# 60_WIFI_RTL8723DS.net
KiCad netlist of a schematic drawn in Altium Designer
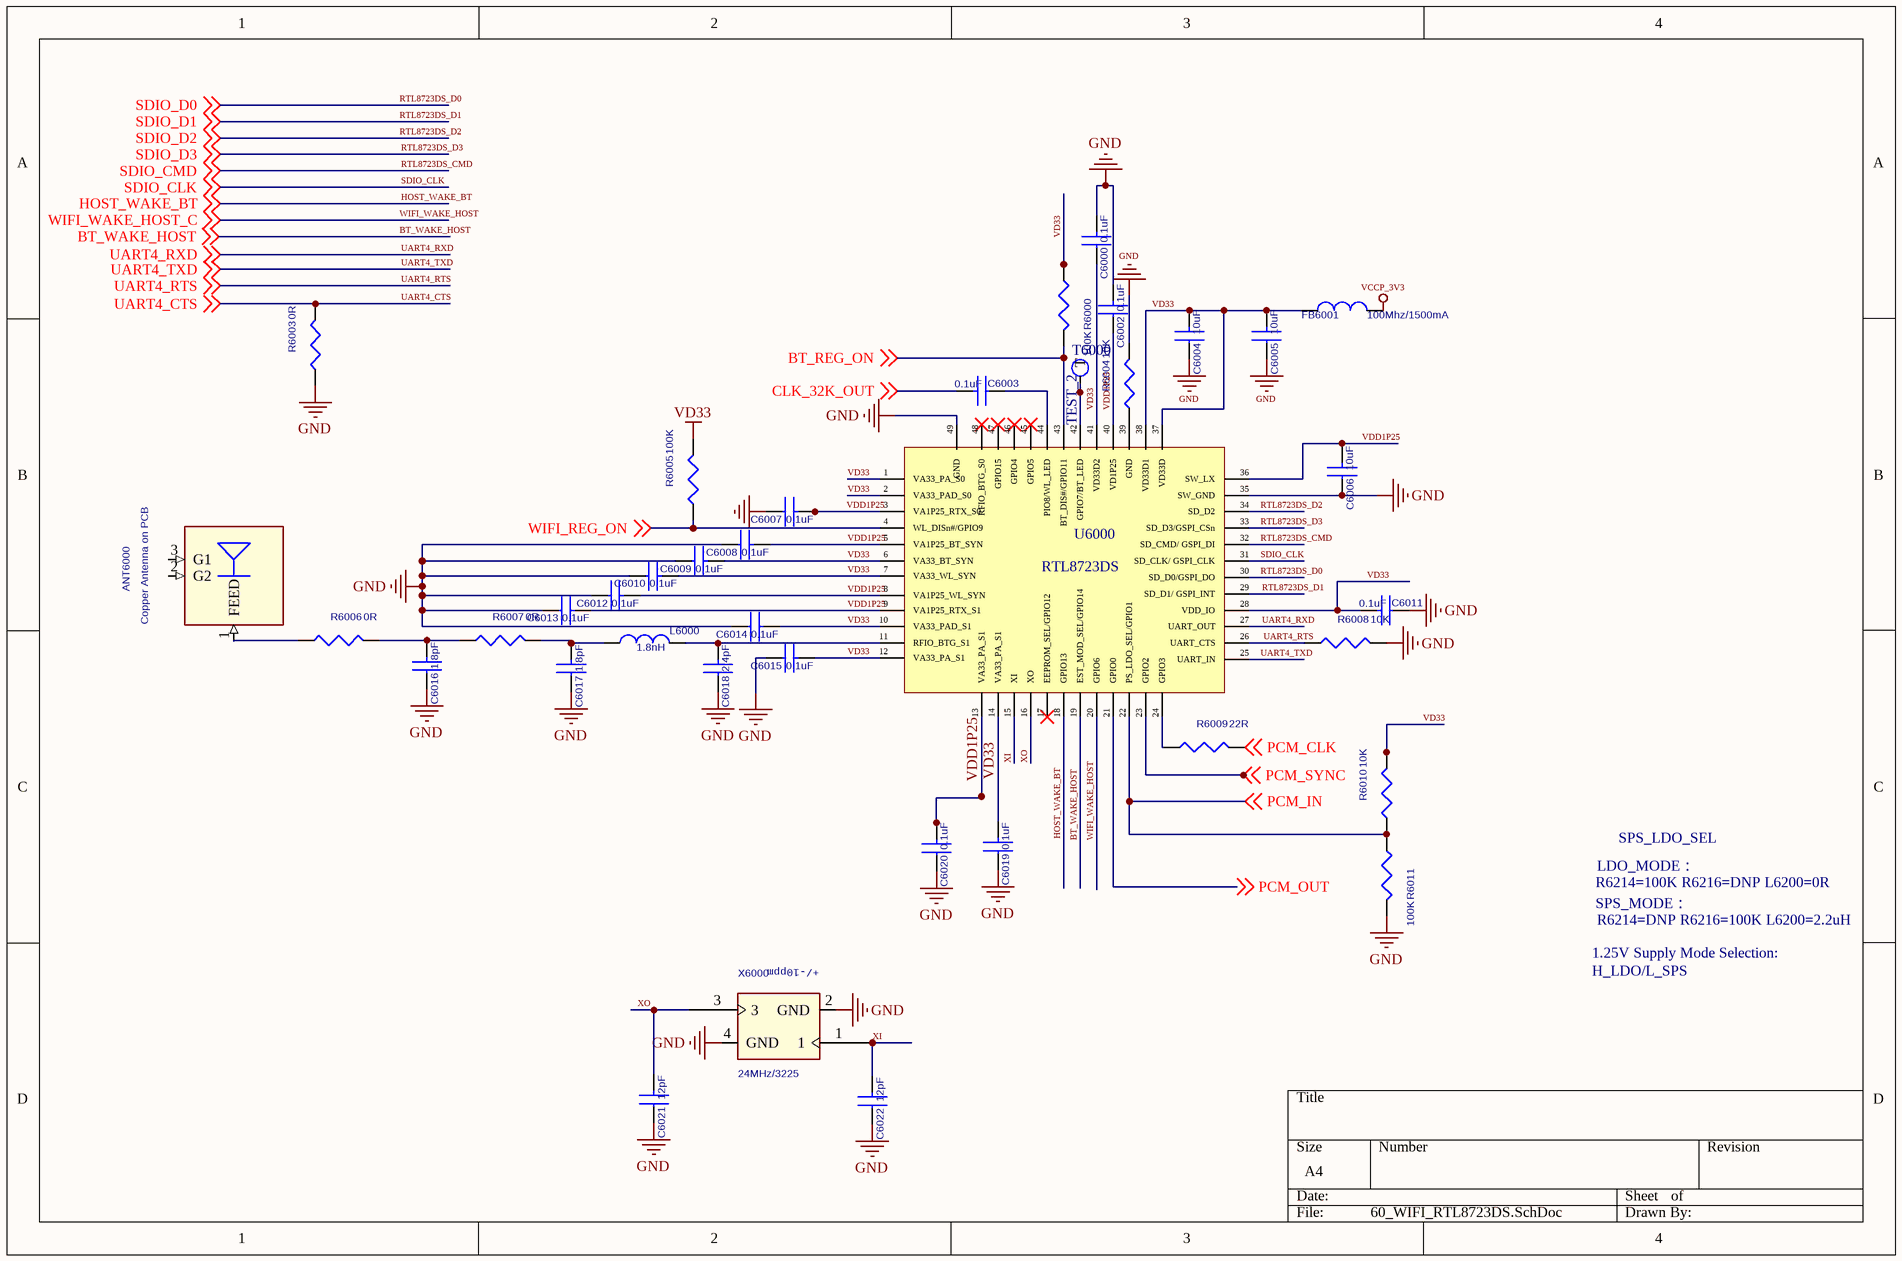
[diagram p0: 60_WIFI_RTL8723DS.SchDoc]

(export (version "E")
  (design (tool "Eeschema 10.0.6"))
  (components
    (comp (ref "ANT6000")
      (value "N/A")
      (footprint "ANT")
      (fields
        (field (name "MANUFACTURER PART NUMBER") "IIFA_CC2420")
        (field (name "NOTE") "Copper Antenna on PCB")
      )
      (libsource (lib "RK3128(Y2)_2X16BIT_V0_1_20201001") (part "ANT_IIFA_CC2420_32mil_MIR"))
    )
    (comp (ref "C6000") (value "0.1uF") (footprint "C0402") (libsource (lib "*") (part "C/0603")))
    (comp (ref "C6002") (value "0.1uF") (footprint "C0402") (libsource (lib "*") (part "C/0603")))
    (comp (ref "C6003") (value "0.1uF") (footprint "C0402") (libsource (lib "*") (part "C/0603")))
    (comp (ref "C6004") (value "10uF") (footprint "C0603") (libsource (lib "*") (part "C/0603")))
    (comp (ref "C6005") (value "10uF") (footprint "C0603") (libsource (lib "*") (part "C/0603")))
    (comp (ref "C6006") (value "10uF") (footprint "C0603") (libsource (lib "*") (part "C/0603")))
    (comp (ref "C6007") (value "0.1uF") (footprint "C0402") (libsource (lib "*") (part "C/0603")))
    (comp (ref "C6008") (value "0.1uF") (footprint "C0402") (libsource (lib "*") (part "C/0603")))
    (comp (ref "C6009") (value "0.1uF") (footprint "C0402") (libsource (lib "*") (part "C/0603")))
    (comp (ref "C6010") (value "0.1uF") (footprint "C0402") (libsource (lib "*") (part "C/0603")))
    (comp (ref "C6011") (value "0.1uF") (footprint "C0402") (libsource (lib "*") (part "C/0603")))
    (comp (ref "C6012") (value "0.1uF") (footprint "C0402") (libsource (lib "*") (part "C/0603")))
    (comp (ref "C6013") (value "0.1uF") (footprint "C0402") (libsource (lib "*") (part "C/0603")))
    (comp (ref "C6014") (value "0.1uF") (footprint "C0402") (libsource (lib "*") (part "C/0603")))
    (comp (ref "C6015") (value "0.1uF") (footprint "C0402") (libsource (lib "*") (part "C/0603")))
    (comp (ref "C6016") (value "1.8pF") (footprint "C0402") (libsource (lib "*") (part "C/0603")))
    (comp (ref "C6017") (value "1.8pF") (footprint "C0402") (libsource (lib "*") (part "C/0603")))
    (comp (ref "C6018") (value "2.4pF") (footprint "C0402") (libsource (lib "*") (part "C/0603")))
    (comp (ref "C6019") (value "0.1uF") (footprint "C0402") (libsource (lib "*") (part "C/0603")))
    (comp (ref "C6020") (value "0.1uF") (footprint "C0402") (libsource (lib "*") (part "C/0603")))
    (comp (ref "C6021") (value "12pF") (footprint "C0402") (libsource (lib "*") (part "C/0603")))
    (comp (ref "C6022") (value "12pF") (footprint "C0402") (libsource (lib "*") (part "C/0603")))
    (comp (ref "FB6001") (value "100Mhz/1500mA") (footprint "L0603") (libsource (lib "*") (part "L/0603")))
    (comp (ref "L6000") (value "1.8nH") (footprint "R0402") (libsource (lib "*") (part "L/0402")))
    (comp (ref "R6000") (value "100K") (footprint "R0402") (libsource (lib "*") (part "R/0402(H)")))
    (comp (ref "R6003") (value "0R") (footprint "R0402") (libsource (lib "*") (part "R/0402(H)")))
    (comp (ref "R6004") (value "10K") (footprint "R0402") (libsource (lib "*") (part "R/0402(H)")))
    (comp (ref "R6005") (value "100K") (footprint "R0402") (libsource (lib "*") (part "R/0402(H)")))
    (comp (ref "R6006") (value "0R") (footprint "R0402") (libsource (lib "*") (part "R/0402(H)")))
    (comp (ref "R6007") (value "0R") (footprint "R0402") (libsource (lib "*") (part "R/0402(H)")))
    (comp (ref "R6008") (value "10K") (footprint "R0402") (libsource (lib "*") (part "R/0402(H)")))
    (comp (ref "R6009") (value "22R") (footprint "R0402") (libsource (lib "*") (part "R/0402(H)")))
    (comp (ref "R6010") (value "10K") (footprint "R0402") (libsource (lib "*") (part "R/0402(H)")))
    (comp (ref "R6011") (value "100K") (footprint "R0402") (libsource (lib "*") (part "R/0402(H)")))
    (comp (ref "T6000") (value "TEST_2") (footprint "TEST") (libsource (lib "amenuo") (part "TEST_2")))
    (comp (ref "U6000")
      (value "RTL8723DS")
      (footprint "RTL8723DS")
      (libsource (lib "amenuo") (part "RTL8723DS"))
    )
    (comp (ref "X6000")
      (value "24MHz/3225")
      (footprint "CRY-D3225")
      (libsource (lib "*") (part "XTAL/26MHz/3225"))
    )
  )
  (nets
    (net (code "2") (name "/VDD1P25") (class "Default")
      (node (ref "C6002") (pin "1") (pinfunction "1_1") (pintype "passive"))
      (node (ref "C6006") (pin "2") (pinfunction "2_2") (pintype "passive"))
      (node (ref "C6007") (pin "2") (pinfunction "2_2") (pintype "passive"))
      (node (ref "C6008") (pin "2") (pinfunction "2_2") (pintype "passive"))
      (node (ref "C6012") (pin "2") (pinfunction "2_2") (pintype "passive"))
      (node (ref "C6013") (pin "2") (pinfunction "2_2") (pintype "passive"))
      (node (ref "C6020") (pin "2") (pinfunction "2_2") (pintype "passive"))
      (node (ref "U6000") (pin "13") (pinfunction "VA33_PA_S1_13") (pintype "passive"))
      (node (ref "U6000") (pin "3") (pinfunction "VA1P25_RTX_S0_3") (pintype "passive"))
      (node (ref "U6000") (pin "36") (pinfunction "SW_LX_36") (pintype "passive"))
      (node (ref "U6000") (pin "40") (pinfunction "VD1P25_40") (pintype "passive"))
      (node (ref "U6000") (pin "5") (pinfunction "VA1P25_BT_SYN_5") (pintype "passive"))
      (node (ref "U6000") (pin "8") (pinfunction "VA1P25_WL_SYN_8") (pintype "passive"))
      (node (ref "U6000") (pin "9") (pinfunction "VA1P25_RTX_S1_9") (pintype "passive"))
    )
    (net (code "3") (name "/XI") (class "Default")
      (node (ref "C6022") (pin "2") (pinfunction "2_2") (pintype "passive"))
      (node (ref "U6000") (pin "15") (pinfunction "XI_15") (pintype "passive"))
      (node (ref "X6000") (pin "1") (pinfunction "1_1") (pintype "passive"))
    )
    (net (code "4") (name "/XO") (class "Default")
      (node (ref "C6021") (pin "2") (pinfunction "2_2") (pintype "passive"))
      (node (ref "U6000") (pin "16") (pinfunction "XO_16") (pintype "passive"))
      (node (ref "X6000") (pin "3") (pinfunction "3_3") (pintype "passive"))
    )
    (net (code "5") (name "BT_REG_ON") (class "Default")
      (node (ref "R6000") (pin "2") (pinfunction "2_2") (pintype "passive"))
      (node (ref "U6000") (pin "43") (pinfunction "BT_DIS#/GPIO11_43") (pintype "passive"))
    )
    (net (code "6") (name "BT_WAKE_HOST") (class "Default")
      (node (ref "U6000") (pin "19") (pinfunction "EST_MOD_SEL/GPIO14_19") (pintype "passive"))
    )
    (net (code "7") (name "CLK_32K_OUT") (class "Default")
      (node (ref "C6003") (pin "2") (pinfunction "2_2") (pintype "passive"))
    )
    (net (code "8") (name "GND") (class "Default")
      (node (ref "C6000") (pin "2") (pinfunction "2_2") (pintype "passive"))
      (node (ref "C6002") (pin "2") (pinfunction "2_2") (pintype "passive"))
      (node (ref "C6004") (pin "1") (pinfunction "1_1") (pintype "passive"))
      (node (ref "C6005") (pin "1") (pinfunction "1_1") (pintype "passive"))
      (node (ref "C6006") (pin "1") (pinfunction "1_1") (pintype "passive"))
      (node (ref "C6007") (pin "1") (pinfunction "1_1") (pintype "passive"))
      (node (ref "C6008") (pin "1") (pinfunction "1_1") (pintype "passive"))
      (node (ref "C6009") (pin "1") (pinfunction "1_1") (pintype "passive"))
      (node (ref "C6010") (pin "1") (pinfunction "1_1") (pintype "passive"))
      (node (ref "C6011") (pin "1") (pinfunction "1_1") (pintype "passive"))
      (node (ref "C6012") (pin "1") (pinfunction "1_1") (pintype "passive"))
      (node (ref "C6013") (pin "1") (pinfunction "1_1") (pintype "passive"))
      (node (ref "C6014") (pin "1") (pinfunction "1_1") (pintype "passive"))
      (node (ref "C6015") (pin "1") (pinfunction "1_1") (pintype "passive"))
      (node (ref "C6016") (pin "1") (pinfunction "1_1") (pintype "passive"))
      (node (ref "C6017") (pin "1") (pinfunction "1_1") (pintype "passive"))
      (node (ref "C6018") (pin "1") (pinfunction "1_1") (pintype "passive"))
      (node (ref "C6019") (pin "1") (pinfunction "1_1") (pintype "passive"))
      (node (ref "C6020") (pin "1") (pinfunction "1_1") (pintype "passive"))
      (node (ref "C6021") (pin "1") (pinfunction "1_1") (pintype "passive"))
      (node (ref "C6022") (pin "1") (pinfunction "1_1") (pintype "passive"))
      (node (ref "R6003") (pin "1") (pinfunction "1_1") (pintype "passive"))
      (node (ref "R6004") (pin "2") (pinfunction "2_2") (pintype "passive"))
      (node (ref "R6008") (pin "2") (pinfunction "2_2") (pintype "passive"))
      (node (ref "R6011") (pin "2") (pinfunction "2_2") (pintype "passive"))
      (node (ref "U6000") (pin "35") (pinfunction "SW_GND_35") (pintype "passive"))
      (node (ref "U6000") (pin "49") (pinfunction "GND_49") (pintype "passive"))
      (node (ref "X6000") (pin "2") (pinfunction "GND_2") (pintype "passive"))
      (node (ref "X6000") (pin "4") (pinfunction "GND_4") (pintype "passive"))
    )
    (net (code "9") (name "HOST_WAKE_BT") (class "Default")
      (node (ref "U6000") (pin "18") (pinfunction "GPIO13_18") (pintype "passive"))
    )
    (net (code "10") (name "Net-(ANT6000-FEED)") (class "Default")
      (node (ref "ANT6000") (pin "1") (pinfunction "FEED_1") (pintype "input"))
      (node (ref "R6006") (pin "1") (pinfunction "1_1") (pintype "passive"))
    )
    (net (code "11") (name "Net-(C6016-Pad2)") (class "Default")
      (node (ref "C6016") (pin "2") (pinfunction "2_2") (pintype "passive"))
      (node (ref "R6006") (pin "2") (pinfunction "2_2") (pintype "passive"))
      (node (ref "R6007") (pin "1") (pinfunction "1_1") (pintype "passive"))
    )
    (net (code "12") (name "Net-(C6017-Pad2)") (class "Default")
      (node (ref "C6017") (pin "2") (pinfunction "2_2") (pintype "passive"))
      (node (ref "L6000") (pin "1") (pinfunction "1_1") (pintype "passive"))
      (node (ref "R6007") (pin "2") (pinfunction "2_2") (pintype "passive"))
    )
    (net (code "13") (name "Net-(R6004-Pad1)") (class "Default")
      (node (ref "R6004") (pin "1") (pinfunction "1_1") (pintype "passive"))
      (node (ref "U6000") (pin "39") (pinfunction "GND_39") (pintype "passive"))
    )
    (net (code "14") (name "Net-(T6000-T)") (class "Default")
      (node (ref "T6000") (pin "1") (pinfunction "T_1") (pintype "passive"))
      (node (ref "U6000") (pin "42") (pinfunction "GPIO7/BT_LED_42") (pintype "passive"))
    )
    (net (code "15") (name "Net-(U6000-GPIO3)") (class "Default")
      (node (ref "R6009") (pin "1") (pinfunction "1_1") (pintype "passive"))
      (node (ref "U6000") (pin "24") (pinfunction "GPIO3_24") (pintype "passive"))
    )
    (net (code "16") (name "Net-(U6000-PIO8{slash}WL_LED)") (class "Default")
      (node (ref "C6003") (pin "1") (pinfunction "1_1") (pintype "passive"))
      (node (ref "U6000") (pin "44") (pinfunction "PIO8/WL_LED_44") (pintype "passive"))
    )
    (net (code "17") (name "Net-(U6000-RFIO_BTG_S1)") (class "Default")
      (node (ref "C6018") (pin "2") (pinfunction "2_2") (pintype "passive"))
      (node (ref "L6000") (pin "2") (pinfunction "2_2") (pintype "passive"))
      (node (ref "U6000") (pin "11") (pinfunction "RFIO_BTG_S1_11") (pintype "passive"))
    )
    (net (code "18") (name "PCM_CLK") (class "Default")
      (node (ref "R6009") (pin "2") (pinfunction "2_2") (pintype "passive"))
    )
    (net (code "19") (name "PCM_IN") (class "Default")
      (node (ref "R6010") (pin "1") (pinfunction "1_1") (pintype "passive"))
      (node (ref "R6011") (pin "1") (pinfunction "1_1") (pintype "passive"))
      (node (ref "U6000") (pin "22") (pinfunction "PS_LDO_SEL/GPIO1_22") (pintype "passive"))
    )
    (net (code "20") (name "PCM_OUT") (class "Default")
      (node (ref "U6000") (pin "21") (pinfunction "GPIO0_21") (pintype "passive"))
    )
    (net (code "21") (name "PCM_SYNC") (class "Default")
      (node (ref "U6000") (pin "23") (pinfunction "GPIO2_23") (pintype "passive"))
    )
    (net (code "22") (name "SDIO_CLK") (class "Default")
      (node (ref "U6000") (pin "31") (pinfunction "SD_CLK/_GSPI_CLK_31") (pintype "passive"))
    )
    (net (code "23") (name "SDIO_CMD") (class "Default")
      (node (ref "U6000") (pin "32") (pinfunction "SD_CMD/_GSPI_DI_32") (pintype "passive"))
    )
    (net (code "24") (name "SDIO_D0") (class "Default")
      (node (ref "U6000") (pin "30") (pinfunction "SD_D0/GSPI_DO_30") (pintype "passive"))
    )
    (net (code "25") (name "SDIO_D1") (class "Default")
      (node (ref "U6000") (pin "29") (pinfunction "SD_D1/_GSPI_INT_29") (pintype "passive"))
    )
    (net (code "26") (name "SDIO_D2") (class "Default")
      (node (ref "U6000") (pin "34") (pinfunction "SD_D2_34") (pintype "passive"))
    )
    (net (code "27") (name "SDIO_D3") (class "Default")
      (node (ref "U6000") (pin "33") (pinfunction "SD_D3/GSPI_CSn_33") (pintype "passive"))
    )
    (net (code "28") (name "UART4_CTS") (class "Default")
      (node (ref "R6003") (pin "2") (pinfunction "2_2") (pintype "passive"))
    )
    (net (code "29") (name "UART4_RTS") (class "Default")
      (node (ref "R6008") (pin "1") (pinfunction "1_1") (pintype "passive"))
      (node (ref "U6000") (pin "26") (pinfunction "UART_CTS_26") (pintype "passive"))
    )
    (net (code "30") (name "UART4_RXD") (class "Default")
      (node (ref "U6000") (pin "27") (pinfunction "UART_OUT_27") (pintype "passive"))
    )
    (net (code "31") (name "UART4_TXD") (class "Default")
      (node (ref "U6000") (pin "25") (pinfunction "UART_IN_25") (pintype "passive"))
    )
    (net (code "32") (name "VCCP_3V3") (class "Default")
      (node (ref "FB6001") (pin "2") (pinfunction "2_2") (pintype "passive"))
    )
    (net (code "33") (name "VD33") (class "Default")
      (node (ref "C6000") (pin "1") (pinfunction "1_1") (pintype "passive"))
      (node (ref "C6004") (pin "2") (pinfunction "2_2") (pintype "passive"))
      (node (ref "C6005") (pin "2") (pinfunction "2_2") (pintype "passive"))
      (node (ref "C6009") (pin "2") (pinfunction "2_2") (pintype "passive"))
      (node (ref "C6010") (pin "2") (pinfunction "2_2") (pintype "passive"))
      (node (ref "C6011") (pin "2") (pinfunction "2_2") (pintype "passive"))
      (node (ref "C6014") (pin "2") (pinfunction "2_2") (pintype "passive"))
      (node (ref "C6015") (pin "2") (pinfunction "2_2") (pintype "passive"))
      (node (ref "C6019") (pin "2") (pinfunction "2_2") (pintype "passive"))
      (node (ref "FB6001") (pin "1") (pinfunction "1_1") (pintype "passive"))
      (node (ref "R6000") (pin "1") (pinfunction "1_1") (pintype "passive"))
      (node (ref "R6005") (pin "2") (pinfunction "2_2") (pintype "passive"))
      (node (ref "R6010") (pin "2") (pinfunction "2_2") (pintype "passive"))
      (node (ref "U6000") (pin "1") (pinfunction "VA33_PA_S0_1") (pintype "passive"))
      (node (ref "U6000") (pin "10") (pinfunction "VA33_PAD_S1_10") (pintype "passive"))
      (node (ref "U6000") (pin "12") (pinfunction "VA33_PA_S1_12") (pintype "passive"))
      (node (ref "U6000") (pin "14") (pinfunction "VA33_PA_S1_14") (pintype "passive"))
      (node (ref "U6000") (pin "2") (pinfunction "VA33_PAD_S0_2") (pintype "passive"))
      (node (ref "U6000") (pin "28") (pinfunction "VDD_IO_28") (pintype "passive"))
      (node (ref "U6000") (pin "37") (pinfunction "VD33D_37") (pintype "passive"))
      (node (ref "U6000") (pin "38") (pinfunction "VD33D1_38") (pintype "passive"))
      (node (ref "U6000") (pin "41") (pinfunction "VD33D2_41") (pintype "passive"))
      (node (ref "U6000") (pin "6") (pinfunction "VA33_BT_SYN_6") (pintype "passive"))
      (node (ref "U6000") (pin "7") (pinfunction "VA33_WL_SYN_7") (pintype "passive"))
    )
    (net (code "34") (name "WIFI_REG_ON") (class "Default")
      (node (ref "R6005") (pin "1") (pinfunction "1_1") (pintype "passive"))
      (node (ref "U6000") (pin "4") (pinfunction "WL_DISn#/GPIO9_4") (pintype "passive"))
    )
    (net (code "35") (name "WIFI_WAKE_HOST_C") (class "Default")
      (node (ref "U6000") (pin "20") (pinfunction "GPIO6_20") (pintype "passive"))
    )
    (net (code "36") (name "unconnected-(ANT6000-G1-Pad3)") (class "Default")
      (node (ref "ANT6000") (pin "3") (pinfunction "G1_3") (pintype "input"))
    )
    (net (code "37") (name "unconnected-(ANT6000-G2-Pad2)") (class "Default")
      (node (ref "ANT6000") (pin "2") (pinfunction "G2_2") (pintype "input"))
    )
    (net (code "38") (name "unconnected-(U6000-EEPROM_SEL{slash}GPIO12-Pad17)") (class "Default")
      (node (ref "U6000") (pin "17") (pinfunction "EEPROM_SEL/GPIO12_17") (pintype "passive+no_connect"))
    )
    (net (code "39") (name "unconnected-(U6000-GPIO4-Pad46)") (class "Default")
      (node (ref "U6000") (pin "46") (pinfunction "GPIO4_46") (pintype "passive+no_connect"))
    )
    (net (code "40") (name "unconnected-(U6000-GPIO5-Pad45)") (class "Default")
      (node (ref "U6000") (pin "45") (pinfunction "GPIO5_45") (pintype "passive+no_connect"))
    )
    (net (code "41") (name "unconnected-(U6000-GPIO15-Pad47)") (class "Default")
      (node (ref "U6000") (pin "47") (pinfunction "GPIO15_47") (pintype "passive+no_connect"))
    )
    (net (code "42") (name "unconnected-(U6000-RFIO_BTG_S0-Pad48)") (class "Default")
      (node (ref "U6000") (pin "48") (pinfunction "RFIO_BTG_S0_48") (pintype "passive+no_connect"))
    )
  )
)
